# UserInterface_0.net
KiCad netlist of a schematic drawn in Altium Designer
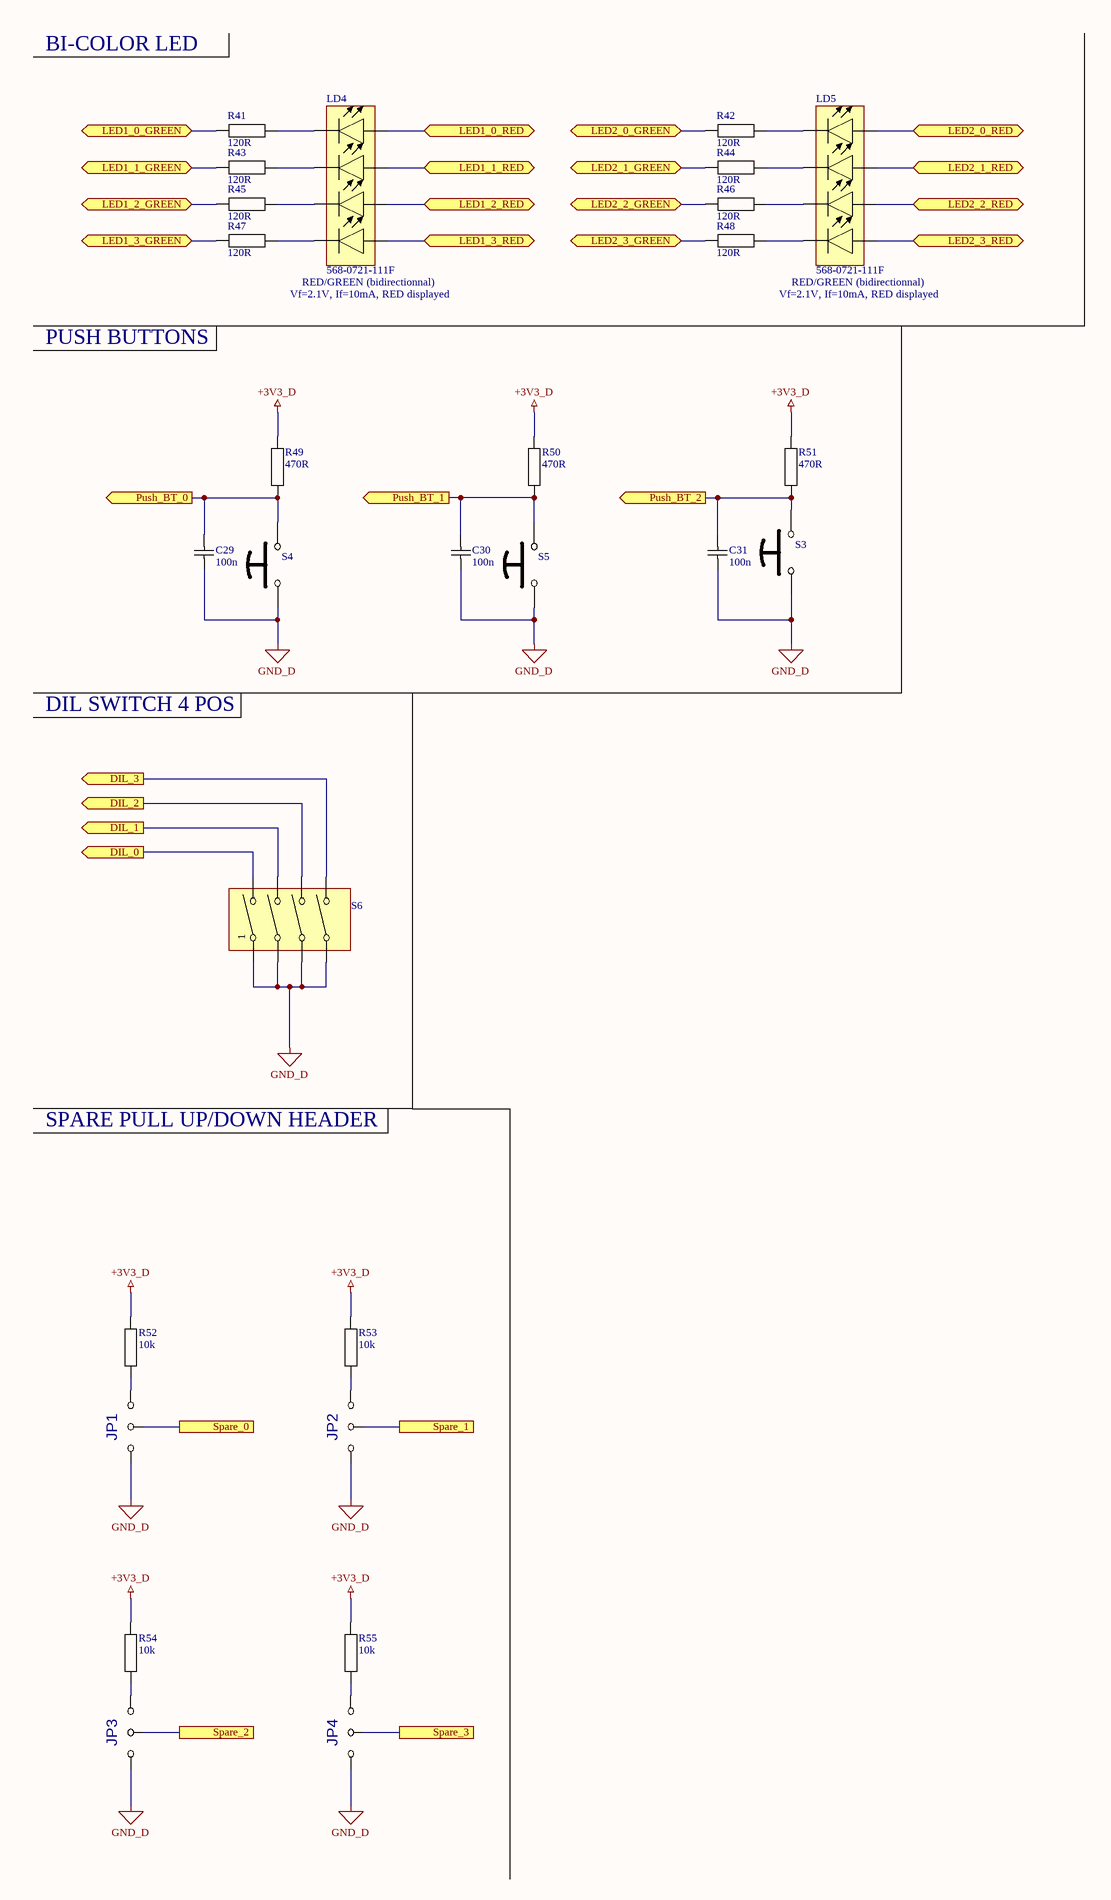
[diagram p0: UserInterface_0.SchDoc, left]
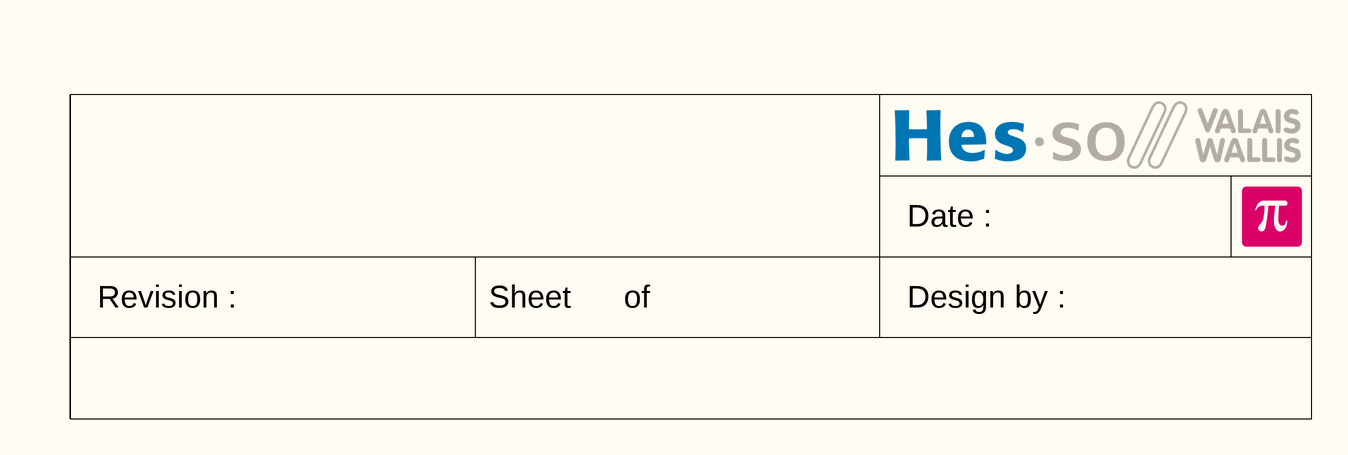
[diagram p1: UserInterface_0.SchDoc, right]

(export (version "E")
  (design (tool "Eeschema 10.0.6"))
  (components
    (comp (ref "C29")
      (value "100n")
      (footprint "CAPACITOR 1608 REFLOW")
      (description "Capacitor X7R 10% 50V 2012(0805)")
      (libsource (lib "Capacitor") (part "Capacitor"))
    )
    (comp (ref "C30")
      (value "100n")
      (footprint "CAPACITOR 1608 REFLOW")
      (description "Capacitor X7R 10% 50V 2012(0805)")
      (libsource (lib "Capacitor") (part "Capacitor"))
    )
    (comp (ref "C31")
      (value "100n")
      (footprint "CAPACITOR 1608 REFLOW")
      (description "Capacitor X7R 10% 50V 2012(0805)")
      (libsource (lib "Capacitor") (part "Capacitor"))
    )
    (comp (ref "JP1")
      (value "{Value}")
      (footprint "JUMPER3 TH")
      (description "JUMPER 3 POS")
      (libsource (lib "Jumper") (part "JUMPER 3 POS"))
    )
    (comp (ref "JP2")
      (value "{Value}")
      (footprint "JUMPER3 TH")
      (description "JUMPER 3 POS")
      (libsource (lib "Jumper") (part "JUMPER 3 POS"))
    )
    (comp (ref "JP3")
      (value "{Value}")
      (footprint "JUMPER3 TH")
      (description "JUMPER 3 POS")
      (libsource (lib "Jumper") (part "JUMPER 3 POS"))
    )
    (comp (ref "JP4")
      (value "{Value}")
      (footprint "JUMPER3 TH")
      (description "JUMPER 3 POS")
      (libsource (lib "Jumper") (part "JUMPER 3 POS"))
    )
    (comp (ref "LD4")
      (value "568-0721-111F")
      (footprint "LED Dialight 568-0721-111")
      (description "LED Dialight 568-0721-111F")
      (fields (field (name "MANUFACTURER") "Dialight"))
      (libsource (lib "Diode") (part "LED Dialight 568-0721-111F"))
    )
    (comp (ref "LD5")
      (value "568-0721-111F")
      (footprint "LED Dialight 568-0721-111")
      (description "LED Dialight 568-0721-111F")
      (fields (field (name "MANUFACTURER") "Dialight"))
      (libsource (lib "Diode") (part "LED Dialight 568-0721-111F"))
    )
    (comp (ref "R41")
      (value "120R")
      (footprint "RESISTOR 1608 REFLOW")
      (description "Resistor 1% 50V 100mW 1608(0603)")
      (libsource (lib "Resistor") (part "Resistor"))
    )
    (comp (ref "R42")
      (value "120R")
      (footprint "RESISTOR 1608 REFLOW")
      (description "Resistor 1% 50V 100mW 1608(0603)")
      (libsource (lib "Resistor") (part "Resistor"))
    )
    (comp (ref "R43")
      (value "120R")
      (footprint "RESISTOR 1608 REFLOW")
      (description "Resistor 1% 50V 100mW 1608(0603)")
      (libsource (lib "Resistor") (part "Resistor"))
    )
    (comp (ref "R44")
      (value "120R")
      (footprint "RESISTOR 1608 REFLOW")
      (description "Resistor 1% 50V 100mW 1608(0603)")
      (libsource (lib "Resistor") (part "Resistor"))
    )
    (comp (ref "R45")
      (value "120R")
      (footprint "RESISTOR 1608 REFLOW")
      (description "Resistor 1% 50V 100mW 1608(0603)")
      (libsource (lib "Resistor") (part "Resistor"))
    )
    (comp (ref "R46")
      (value "120R")
      (footprint "RESISTOR 1608 REFLOW")
      (description "Resistor 1% 50V 100mW 1608(0603)")
      (libsource (lib "Resistor") (part "Resistor"))
    )
    (comp (ref "R47")
      (value "120R")
      (footprint "RESISTOR 1608 REFLOW")
      (description "Resistor 1% 50V 100mW 1608(0603)")
      (libsource (lib "Resistor") (part "Resistor"))
    )
    (comp (ref "R48")
      (value "120R")
      (footprint "RESISTOR 1608 REFLOW")
      (description "Resistor 1% 50V 100mW 1608(0603)")
      (libsource (lib "Resistor") (part "Resistor"))
    )
    (comp (ref "R49")
      (value "470R")
      (footprint "RESISTOR 2012 REFLOW")
      (description "Resistor 1% 50V 125mW 2012(0805)")
      (libsource (lib "Resistor") (part "Resistor"))
    )
    (comp (ref "R50")
      (value "470R")
      (footprint "RESISTOR 2012 REFLOW")
      (description "Resistor 1% 50V 125mW 2012(0805)")
      (libsource (lib "Resistor") (part "Resistor"))
    )
    (comp (ref "R51")
      (value "470R")
      (footprint "RESISTOR 2012 REFLOW")
      (description "Resistor 1% 50V 125mW 2012(0805)")
      (libsource (lib "Resistor") (part "Resistor"))
    )
    (comp (ref "R52")
      (value "10k")
      (footprint "RESISTOR 2012 REFLOW")
      (description "Resistor 1% 50V 125mW 2012(0805)")
      (libsource (lib "Resistor") (part "Resistor"))
    )
    (comp (ref "R53")
      (value "10k")
      (footprint "RESISTOR 2012 REFLOW")
      (description "Resistor 1% 50V 125mW 2012(0805)")
      (libsource (lib "Resistor") (part "Resistor"))
    )
    (comp (ref "R54")
      (value "10k")
      (footprint "RESISTOR 2012 REFLOW")
      (description "Resistor 1% 50V 125mW 2012(0805)")
      (libsource (lib "Resistor") (part "Resistor"))
    )
    (comp (ref "R55")
      (value "10k")
      (footprint "RESISTOR 2012 REFLOW")
      (description "Resistor 1% 50V 125mW 2012(0805)")
      (libsource (lib "Resistor") (part "Resistor"))
    )
    (comp (ref "S3")
      (value "FSMRA4JH04")
      (footprint "Push Button C7.1x3.7 TE FSMRA4JH")
      (description "Push Button, 2 pins")
      (fields (field (name "MANUFACTURER") "TE Connectivity / Alcoswitch"))
      (libsource (lib "Button") (part "Push Button 2Pins"))
    )
    (comp (ref "S4")
      (value "FSMRA4JH04")
      (footprint "Push Button C7.1x3.7 TE FSMRA4JH")
      (description "Push Button, 2 pins")
      (fields (field (name "MANUFACTURER") "TE Connectivity / Alcoswitch"))
      (libsource (lib "Button") (part "Push Button 2Pins"))
    )
    (comp (ref "S5")
      (value "FSMRA4JH04")
      (footprint "Push Button C7.1x3.7 TE FSMRA4JH")
      (description "Push Button, 2 pins")
      (fields (field (name "MANUFACTURER") "TE Connectivity / Alcoswitch"))
      (libsource (lib "Button") (part "Push Button 2Pins"))
    )
    (comp (ref "S6")
      (value "*")
      (footprint "DIP SWITCH MULTICOMP  MCDHN-04F")
      (description "MULTICOMP  MCDHN-04F")
      (libsource (lib "Button") (part "DIP Switch 4Pos"))
    )
  )
  (nets
    (net (code "1") (name "+3V3_D") (class "Default")
      (node (ref "R49") (pin "2") (pinfunction "2_2") (pintype "passive"))
      (node (ref "R50") (pin "2") (pinfunction "2_2") (pintype "passive"))
      (node (ref "R51") (pin "2") (pinfunction "2_2") (pintype "passive"))
      (node (ref "R52") (pin "2") (pinfunction "2_2") (pintype "passive"))
      (node (ref "R53") (pin "2") (pinfunction "2_2") (pintype "passive"))
      (node (ref "R54") (pin "2") (pinfunction "2_2") (pintype "passive"))
      (node (ref "R55") (pin "2") (pinfunction "2_2") (pintype "passive"))
    )
    (net (code "2") (name "/DIL_0") (class "Default")
      (node (ref "S6") (pin "2") (pinfunction "2_2") (pintype "passive"))
    )
    (net (code "3") (name "/DIL_1") (class "Default")
      (node (ref "S6") (pin "4") (pinfunction "4_4") (pintype "passive"))
    )
    (net (code "4") (name "/DIL_2") (class "Default")
      (node (ref "S6") (pin "6") (pinfunction "6_6") (pintype "passive"))
    )
    (net (code "5") (name "/DIL_3") (class "Default")
      (node (ref "S6") (pin "8") (pinfunction "8_8") (pintype "passive"))
    )
    (net (code "6") (name "/LED1_0_GREEN") (class "Default")
      (node (ref "R41") (pin "1") (pinfunction "1_1") (pintype "passive"))
    )
    (net (code "7") (name "/LED1_0_RED") (class "Default")
      (node (ref "LD4") (pin "8") (pinfunction "A_8") (pintype "passive"))
    )
    (net (code "8") (name "/LED1_1_GREEN") (class "Default")
      (node (ref "R43") (pin "1") (pinfunction "1_1") (pintype "passive"))
    )
    (net (code "9") (name "/LED1_1_RED") (class "Default")
      (node (ref "LD4") (pin "6") (pinfunction "A_6") (pintype "passive"))
    )
    (net (code "10") (name "/LED1_2_GREEN") (class "Default")
      (node (ref "R45") (pin "1") (pinfunction "1_1") (pintype "passive"))
    )
    (net (code "11") (name "/LED1_2_RED") (class "Default")
      (node (ref "LD4") (pin "4") (pinfunction "A_4") (pintype "passive"))
    )
    (net (code "12") (name "/LED1_3_GREEN") (class "Default")
      (node (ref "R47") (pin "1") (pinfunction "1_1") (pintype "passive"))
    )
    (net (code "13") (name "/LED1_3_RED") (class "Default")
      (node (ref "LD4") (pin "2") (pinfunction "A_2") (pintype "passive"))
    )
    (net (code "14") (name "/LED2_0_GREEN") (class "Default")
      (node (ref "R42") (pin "1") (pinfunction "1_1") (pintype "passive"))
    )
    (net (code "15") (name "/LED2_0_RED") (class "Default")
      (node (ref "LD5") (pin "8") (pinfunction "A_8") (pintype "passive"))
    )
    (net (code "16") (name "/LED2_1_GREEN") (class "Default")
      (node (ref "R44") (pin "1") (pinfunction "1_1") (pintype "passive"))
    )
    (net (code "17") (name "/LED2_1_RED") (class "Default")
      (node (ref "LD5") (pin "6") (pinfunction "A_6") (pintype "passive"))
    )
    (net (code "18") (name "/LED2_2_GREEN") (class "Default")
      (node (ref "R46") (pin "1") (pinfunction "1_1") (pintype "passive"))
    )
    (net (code "19") (name "/LED2_2_RED") (class "Default")
      (node (ref "LD5") (pin "4") (pinfunction "A_4") (pintype "passive"))
    )
    (net (code "20") (name "/LED2_3_GREEN") (class "Default")
      (node (ref "R48") (pin "1") (pinfunction "1_1") (pintype "passive"))
    )
    (net (code "21") (name "/LED2_3_RED") (class "Default")
      (node (ref "LD5") (pin "2") (pinfunction "A_2") (pintype "passive"))
    )
    (net (code "22") (name "/Push_BT_0") (class "Default")
      (node (ref "C29") (pin "2") (pinfunction "2_2") (pintype "passive"))
      (node (ref "R49") (pin "1") (pinfunction "1_1") (pintype "passive"))
      (node (ref "S4") (pin "2") (pinfunction "2_2") (pintype "passive"))
    )
    (net (code "23") (name "/Push_BT_1") (class "Default")
      (node (ref "C30") (pin "2") (pinfunction "2_2") (pintype "passive"))
      (node (ref "R50") (pin "1") (pinfunction "1_1") (pintype "passive"))
      (node (ref "S5") (pin "2") (pinfunction "2_2") (pintype "passive"))
    )
    (net (code "24") (name "/Push_BT_2") (class "Default")
      (node (ref "C31") (pin "2") (pinfunction "2_2") (pintype "passive"))
      (node (ref "R51") (pin "1") (pinfunction "1_1") (pintype "passive"))
      (node (ref "S3") (pin "2") (pinfunction "2_2") (pintype "passive"))
    )
    (net (code "25") (name "/Spare_0") (class "Default")
      (node (ref "JP1") (pin "2") (pinfunction "2_2") (pintype "passive"))
    )
    (net (code "26") (name "/Spare_1") (class "Default")
      (node (ref "JP2") (pin "2") (pinfunction "2_2") (pintype "passive"))
    )
    (net (code "27") (name "/Spare_2") (class "Default")
      (node (ref "JP3") (pin "2") (pinfunction "2_2") (pintype "passive"))
    )
    (net (code "28") (name "/Spare_3") (class "Default")
      (node (ref "JP4") (pin "2") (pinfunction "2_2") (pintype "passive"))
    )
    (net (code "29") (name "GND_D") (class "Default")
      (node (ref "C29") (pin "1") (pinfunction "1_1") (pintype "passive"))
      (node (ref "C30") (pin "1") (pinfunction "1_1") (pintype "passive"))
      (node (ref "C31") (pin "1") (pinfunction "1_1") (pintype "passive"))
      (node (ref "JP1") (pin "1") (pinfunction "1_1") (pintype "passive"))
      (node (ref "JP2") (pin "1") (pinfunction "1_1") (pintype "passive"))
      (node (ref "JP3") (pin "1") (pinfunction "1_1") (pintype "passive"))
      (node (ref "JP4") (pin "1") (pinfunction "1_1") (pintype "passive"))
      (node (ref "S3") (pin "1") (pinfunction "1_1") (pintype "passive"))
      (node (ref "S4") (pin "1") (pinfunction "1_1") (pintype "passive"))
      (node (ref "S5") (pin "1") (pinfunction "1_1") (pintype "passive"))
      (node (ref "S6") (pin "1") (pinfunction "1_1") (pintype "passive"))
      (node (ref "S6") (pin "3") (pinfunction "3_3") (pintype "passive"))
      (node (ref "S6") (pin "5") (pinfunction "5_5") (pintype "passive"))
      (node (ref "S6") (pin "7") (pinfunction "7_7") (pintype "passive"))
    )
    (net (code "30") (name "Net-(JP1-Pad3)") (class "Default")
      (node (ref "JP1") (pin "3") (pinfunction "3_3") (pintype "passive"))
      (node (ref "R52") (pin "1") (pinfunction "1_1") (pintype "passive"))
    )
    (net (code "31") (name "Net-(JP2-Pad3)") (class "Default")
      (node (ref "JP2") (pin "3") (pinfunction "3_3") (pintype "passive"))
      (node (ref "R53") (pin "1") (pinfunction "1_1") (pintype "passive"))
    )
    (net (code "32") (name "Net-(JP3-Pad3)") (class "Default")
      (node (ref "JP3") (pin "3") (pinfunction "3_3") (pintype "passive"))
      (node (ref "R54") (pin "1") (pinfunction "1_1") (pintype "passive"))
    )
    (net (code "33") (name "Net-(JP4-Pad3)") (class "Default")
      (node (ref "JP4") (pin "3") (pinfunction "3_3") (pintype "passive"))
      (node (ref "R55") (pin "1") (pinfunction "1_1") (pintype "passive"))
    )
    (net (code "34") (name "Net-(LD4-C-Pad1)") (class "Default")
      (node (ref "LD4") (pin "1") (pinfunction "C_1") (pintype "passive"))
      (node (ref "R47") (pin "2") (pinfunction "2_2") (pintype "passive"))
    )
    (net (code "35") (name "Net-(LD4-C-Pad3)") (class "Default")
      (node (ref "LD4") (pin "3") (pinfunction "C_3") (pintype "passive"))
      (node (ref "R45") (pin "2") (pinfunction "2_2") (pintype "passive"))
    )
    (net (code "36") (name "Net-(LD4-C-Pad5)") (class "Default")
      (node (ref "LD4") (pin "5") (pinfunction "C_5") (pintype "passive"))
      (node (ref "R43") (pin "2") (pinfunction "2_2") (pintype "passive"))
    )
    (net (code "37") (name "Net-(LD4-C-Pad7)") (class "Default")
      (node (ref "LD4") (pin "7") (pinfunction "C_7") (pintype "passive"))
      (node (ref "R41") (pin "2") (pinfunction "2_2") (pintype "passive"))
    )
    (net (code "38") (name "Net-(LD5-C-Pad1)") (class "Default")
      (node (ref "LD5") (pin "1") (pinfunction "C_1") (pintype "passive"))
      (node (ref "R48") (pin "2") (pinfunction "2_2") (pintype "passive"))
    )
    (net (code "39") (name "Net-(LD5-C-Pad3)") (class "Default")
      (node (ref "LD5") (pin "3") (pinfunction "C_3") (pintype "passive"))
      (node (ref "R46") (pin "2") (pinfunction "2_2") (pintype "passive"))
    )
    (net (code "40") (name "Net-(LD5-C-Pad5)") (class "Default")
      (node (ref "LD5") (pin "5") (pinfunction "C_5") (pintype "passive"))
      (node (ref "R44") (pin "2") (pinfunction "2_2") (pintype "passive"))
    )
    (net (code "41") (name "Net-(LD5-C-Pad7)") (class "Default")
      (node (ref "LD5") (pin "7") (pinfunction "C_7") (pintype "passive"))
      (node (ref "R42") (pin "2") (pinfunction "2_2") (pintype "passive"))
    )
  )
)
